# IMU_standalone.net
KiCad netlist of a schematic drawn in Altium Designer
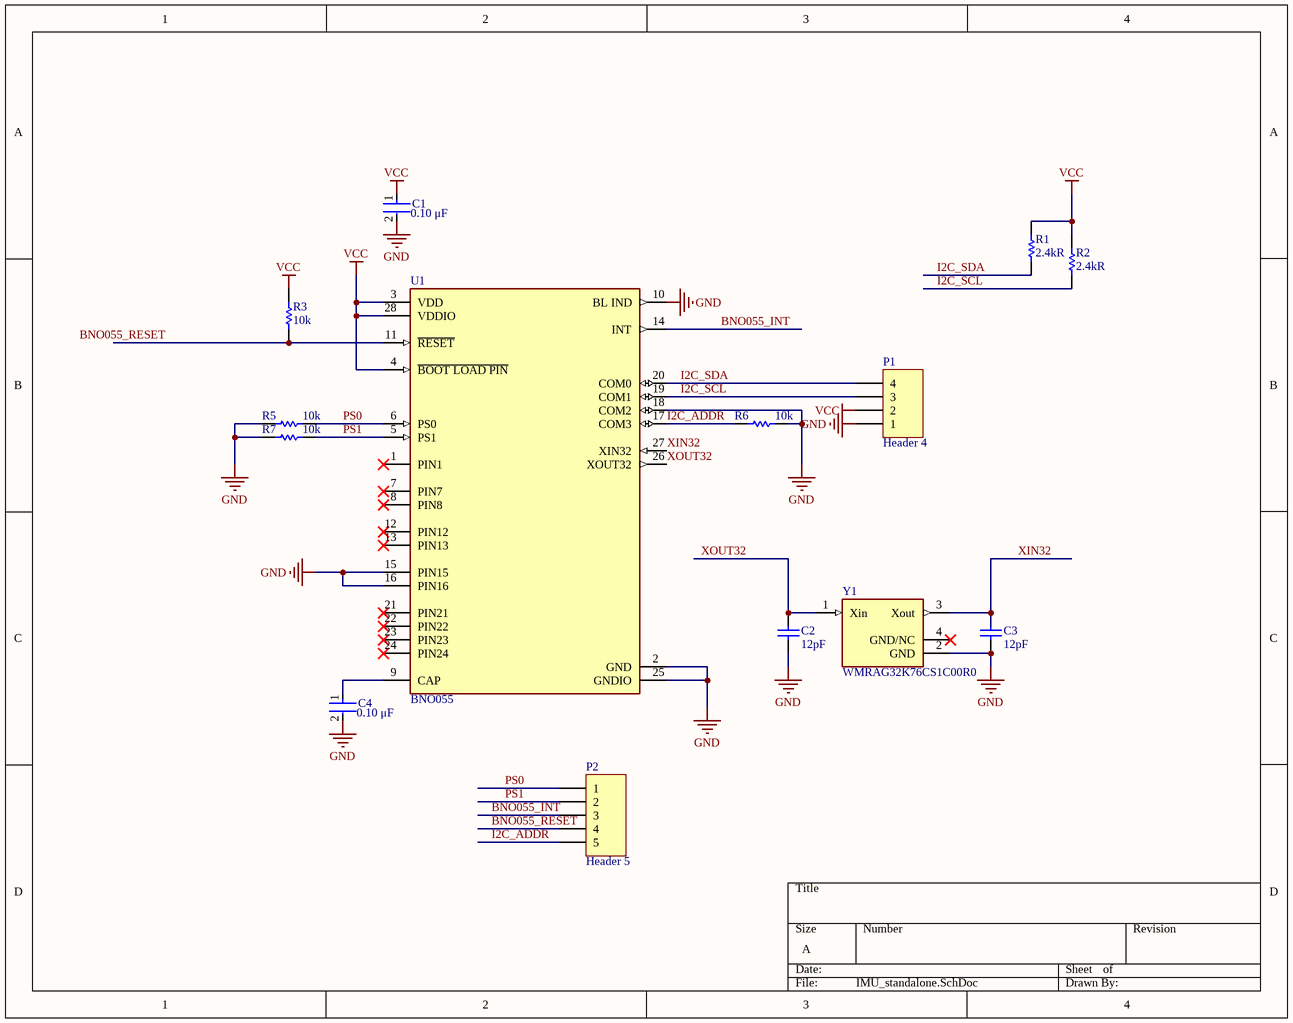
[diagram p0: IMU_standalone.SchDoc]

(export (version "E")
  (design (tool "Eeschema 10.0.6"))
  (components
    (comp (ref "C1")
      (value "C0603C104M4RAC7411")
      (footprint "FP-C0603C-CF-MFG")
      (description "CAP CER 0.1UF 16V X7R 0603")
      (fields
        (field (name "TOLERANCE") "0.2")
        (field (name "CAPACITANCE") "0.10 μF")
        (field (name "MANUFACTURER") "KEMET")
      )
      (libsource (lib "Altium Content Vault") (part "b4654b650e69147ec39a6b967a45e02"))
    )
    (comp (ref "C2")
      (value "12pF")
      (footprint "CAPC1608X90X40NL10T20")
      (description "Chip Capacitor, 12 pF, +/- 5%, 50 V, -55 to 125 degC, 0603 (1608 Metric), RoHS, Tape and Reel")
      (fields (field (name "TOLERANCE") "1%") (field (name "Comment") "CC0603JRNPO9BN120"))
      (libsource (lib "Altium Content Vault") (part "CAP-NP-2"))
    )
    (comp (ref "C3")
      (value "12pF")
      (footprint "CAPC1608X90X40NL10T20")
      (description "Chip Capacitor, 12 pF, +/- 5%, 50 V, -55 to 125 degC, 0603 (1608 Metric), RoHS, Tape and Reel")
      (fields (field (name "TOLERANCE") "1%") (field (name "Comment") "CC0603JRNPO9BN120"))
      (libsource (lib "Altium Content Vault") (part "CAP-NP-2"))
    )
    (comp (ref "C4")
      (value "C0603C104M4RAC7411")
      (footprint "FP-C0603C-CF-MFG")
      (description "CAP CER 0.1UF 16V X7R 0603")
      (fields
        (field (name "TOLERANCE") "0.2")
        (field (name "CAPACITANCE") "0.10 μF")
        (field (name "MANUFACTURER") "KEMET")
      )
      (libsource (lib "Altium Content Vault") (part "b4654b650e69147ec39a6b967a45e02"))
    )
    (comp (ref "P1")
      (value "Header 4")
      (footprint "HDR1X4")
      (description "Header, 4-Pin")
      (fields (field (name "PUBLISHER") "Altium Limited"))
      (libsource (lib "Miscellaneous Connectors") (part "Header 4"))
    )
    (comp (ref "P2")
      (value "Header 5")
      (footprint "HDR1X5")
      (description "Header, 5-Pin")
      (fields (field (name "PUBLISHER") "Altium Limited"))
      (libsource (lib "Miscellaneous Connectors") (part "Header 5"))
    )
    (comp (ref "R1")
      (value "2.4kR")
      (footprint "RESC1608X50X30ML20T20")
      (fields (field (name "PART NUMBER") "RR0816P-242-D") (field (name "MANUFACTURER") "Susumu"))
      (libsource (lib "Altium Content Vault") (part "RES"))
    )
    (comp (ref "R2")
      (value "2.4kR")
      (footprint "RESC1608X50X30ML20T20")
      (fields (field (name "PART NUMBER") "RR0816P-242-D") (field (name "MANUFACTURER") "Susumu"))
      (libsource (lib "Altium Content Vault") (part "RES"))
    )
    (comp (ref "R3")
      (value "10k")
      (footprint "RESC1609X55X30LL15T15")
      (description "Chip Resistor, 10 KOhm, +/- 1%, 0.1 W, -55 to 155 degC, 0603 (1608 Metric), RoHS, Tape and Reel")
      (fields (field (name "TOLERANCE") "1%") (field (name "MANUFACTURER") "Panasonic"))
      (libsource (lib "Altium Content Vault") (part "RES-2"))
    )
    (comp (ref "R5")
      (value "10k")
      (footprint "RESC1609X55X30LL15T15")
      (description "Chip Resistor, 10 KOhm, +/- 1%, 0.1 W, -55 to 155 degC, 0603 (1608 Metric), RoHS, Tape and Reel")
      (fields (field (name "TOLERANCE") "1%") (field (name "MANUFACTURER") "Panasonic"))
      (libsource (lib "Altium Content Vault") (part "RES-2"))
    )
    (comp (ref "R6")
      (value "10k")
      (footprint "RESC1609X55X30LL15T15")
      (description "Chip Resistor, 10 KOhm, +/- 1%, 0.1 W, -55 to 155 degC, 0603 (1608 Metric), RoHS, Tape and Reel")
      (fields (field (name "TOLERANCE") "1%") (field (name "MANUFACTURER") "Panasonic"))
      (libsource (lib "Altium Content Vault") (part "RES-2"))
    )
    (comp (ref "R7")
      (value "10k")
      (footprint "RESC1609X55X30LL15T15")
      (description "Chip Resistor, 10 KOhm, +/- 1%, 0.1 W, -55 to 155 degC, 0603 (1608 Metric), RoHS, Tape and Reel")
      (fields (field (name "TOLERANCE") "1%") (field (name "MANUFACTURER") "Panasonic"))
      (libsource (lib "Altium Content Vault") (part "RES-2"))
    )
    (comp (ref "U1")
      (value "BNO055")
      (footprint "FP-BNO055-MFG")
      (description "IMU ACCEL/GYRO/MAG I2C 28LGA")
      (fields
        (field (name "OCTOPART") "https://octopart.com/bno055-bosch+sensortec-50309911")
        (field (name "VOLTAGE") "1.7~3.6V")
      )
      (libsource (lib "Altium Content Vault") (part "72d621e61db15910e840a84e68b4f76"))
    )
    (comp (ref "Y1")
      (value "WMRAG32K76CS1C00R0")
      (footprint "FP-WMRAG32K76CS1C00R0-MFG")
      (description "MEMS Resonator")
      (fields (field (name "TOLERANCE") "20ppm") (field (name "MANUFACTURER") "Murata"))
      (libsource (lib "Altium Content Vault") (part "f3e38fa55a21b72a83ee03d0b531324"))
    )
  )
  (nets
    (net (code "1") (name "/BNO055_INT") (class "Default")
      (node (ref "P2") (pin "3") (pinfunction "3_3") (pintype "passive"))
      (node (ref "U1") (pin "14") (pinfunction "INT_14") (pintype "output"))
    )
    (net (code "2") (name "/BNO055_RESET") (class "Default")
      (node (ref "P2") (pin "4") (pinfunction "4_4") (pintype "passive"))
      (node (ref "R3") (pin "1") (pinfunction "1_1") (pintype "passive"))
      (node (ref "U1") (pin "11") (pinfunction "~{RESET}_11") (pintype "input"))
    )
    (net (code "3") (name "/I2C_ADDR") (class "Default")
      (node (ref "P2") (pin "5") (pinfunction "5_5") (pintype "passive"))
      (node (ref "R6") (pin "2") (pinfunction "2_2") (pintype "passive"))
      (node (ref "U1") (pin "17") (pinfunction "COM3_17") (pintype "bidirectional"))
    )
    (net (code "4") (name "/I2C_SCL") (class "Default")
      (node (ref "P1") (pin "3") (pinfunction "3_3") (pintype "passive"))
      (node (ref "R2") (pin "1") (pinfunction "1_1") (pintype "passive"))
      (node (ref "U1") (pin "19") (pinfunction "COM1_19") (pintype "bidirectional"))
    )
    (net (code "5") (name "/I2C_SDA") (class "Default")
      (node (ref "P1") (pin "4") (pinfunction "4_4") (pintype "passive"))
      (node (ref "R1") (pin "1") (pinfunction "1_1") (pintype "passive"))
      (node (ref "U1") (pin "20") (pinfunction "COM0_20") (pintype "bidirectional"))
    )
    (net (code "6") (name "/PS0") (class "Default")
      (node (ref "P2") (pin "1") (pinfunction "1_1") (pintype "passive"))
      (node (ref "R5") (pin "2") (pinfunction "2_2") (pintype "passive"))
      (node (ref "U1") (pin "6") (pinfunction "PS0_6") (pintype "input"))
    )
    (net (code "7") (name "/PS1") (class "Default")
      (node (ref "P2") (pin "2") (pinfunction "2_2") (pintype "passive"))
      (node (ref "R7") (pin "2") (pinfunction "2_2") (pintype "passive"))
      (node (ref "U1") (pin "5") (pinfunction "PS1_5") (pintype "input"))
    )
    (net (code "8") (name "/XIN32") (class "Default")
      (node (ref "C3") (pin "2") (pinfunction "2_2") (pintype "passive"))
      (node (ref "U1") (pin "27") (pinfunction "XIN32_27") (pintype "input"))
      (node (ref "Y1") (pin "3") (pinfunction "Xout_3") (pintype "output"))
    )
    (net (code "9") (name "/XOUT32") (class "Default")
      (node (ref "C2") (pin "2") (pinfunction "2_2") (pintype "passive"))
      (node (ref "U1") (pin "26") (pinfunction "XOUT32_26") (pintype "output"))
      (node (ref "Y1") (pin "1") (pinfunction "Xin_1") (pintype "input"))
    )
    (net (code "10") (name "GND") (class "Default")
      (node (ref "C1") (pin "2") (pinfunction "2_2") (pintype "passive"))
      (node (ref "C2") (pin "1") (pinfunction "1_1") (pintype "passive"))
      (node (ref "C3") (pin "1") (pinfunction "1_1") (pintype "passive"))
      (node (ref "C4") (pin "2") (pinfunction "2_2") (pintype "passive"))
      (node (ref "P1") (pin "1") (pinfunction "1_1") (pintype "passive"))
      (node (ref "R5") (pin "1") (pinfunction "1_1") (pintype "passive"))
      (node (ref "R6") (pin "1") (pinfunction "1_1") (pintype "passive"))
      (node (ref "R7") (pin "1") (pinfunction "1_1") (pintype "passive"))
      (node (ref "U1") (pin "10") (pinfunction "BL_IND_10") (pintype "output"))
      (node (ref "U1") (pin "15") (pinfunction "PIN15_15") (pintype "power_in"))
      (node (ref "U1") (pin "16") (pinfunction "PIN16_16") (pintype "power_in"))
      (node (ref "U1") (pin "18") (pinfunction "COM2_18") (pintype "bidirectional"))
      (node (ref "U1") (pin "2") (pinfunction "GND_2") (pintype "power_in"))
      (node (ref "U1") (pin "25") (pinfunction "GNDIO_25") (pintype "power_in"))
      (node (ref "Y1") (pin "2") (pinfunction "GND_2") (pintype "power_in"))
    )
    (net (code "11") (name "Net-(U1-CAP)") (class "Default")
      (node (ref "C4") (pin "1") (pinfunction "1_1") (pintype "passive"))
      (node (ref "U1") (pin "9") (pinfunction "CAP_9") (pintype "passive"))
    )
    (net (code "12") (name "VCC") (class "Default")
      (node (ref "C1") (pin "1") (pinfunction "1_1") (pintype "passive"))
      (node (ref "P1") (pin "2") (pinfunction "2_2") (pintype "passive"))
      (node (ref "R1") (pin "2") (pinfunction "2_2") (pintype "passive"))
      (node (ref "R2") (pin "2") (pinfunction "2_2") (pintype "passive"))
      (node (ref "R3") (pin "2") (pinfunction "2_2") (pintype "passive"))
      (node (ref "U1") (pin "28") (pinfunction "VDDIO_28") (pintype "power_in"))
      (node (ref "U1") (pin "3") (pinfunction "VDD_3") (pintype "power_in"))
      (node (ref "U1") (pin "4") (pinfunction "~{BOOT_LOAD_PIN}_4") (pintype "input"))
    )
    (net (code "13") (name "unconnected-(U1-PIN1-Pad1)") (class "Default")
      (node (ref "U1") (pin "1") (pinfunction "PIN1_1") (pintype "passive+no_connect"))
    )
    (net (code "14") (name "unconnected-(U1-PIN7-Pad7)") (class "Default")
      (node (ref "U1") (pin "7") (pinfunction "PIN7_7") (pintype "passive+no_connect"))
    )
    (net (code "15") (name "unconnected-(U1-PIN8-Pad8)") (class "Default")
      (node (ref "U1") (pin "8") (pinfunction "PIN8_8") (pintype "passive+no_connect"))
    )
    (net (code "16") (name "unconnected-(U1-PIN12-Pad12)") (class "Default")
      (node (ref "U1") (pin "12") (pinfunction "PIN12_12") (pintype "passive+no_connect"))
    )
    (net (code "17") (name "unconnected-(U1-PIN13-Pad13)") (class "Default")
      (node (ref "U1") (pin "13") (pinfunction "PIN13_13") (pintype "passive+no_connect"))
    )
    (net (code "18") (name "unconnected-(U1-PIN21-Pad21)") (class "Default")
      (node (ref "U1") (pin "21") (pinfunction "PIN21_21") (pintype "passive+no_connect"))
    )
    (net (code "19") (name "unconnected-(U1-PIN22-Pad22)") (class "Default")
      (node (ref "U1") (pin "22") (pinfunction "PIN22_22") (pintype "passive+no_connect"))
    )
    (net (code "20") (name "unconnected-(U1-PIN23-Pad23)") (class "Default")
      (node (ref "U1") (pin "23") (pinfunction "PIN23_23") (pintype "passive+no_connect"))
    )
    (net (code "21") (name "unconnected-(U1-PIN24-Pad24)") (class "Default")
      (node (ref "U1") (pin "24") (pinfunction "PIN24_24") (pintype "passive+no_connect"))
    )
    (net (code "22") (name "unconnected-(Y1-GND{slash}NC-Pad4)") (class "Default")
      (node (ref "Y1") (pin "4") (pinfunction "GND/NC_4") (pintype "passive+no_connect"))
    )
  )
)
